# JTAG_Connector.net
KiCad netlist of a schematic drawn in Altium Designer
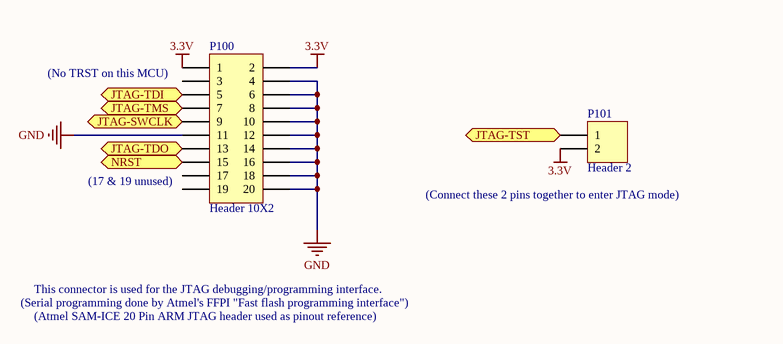
[diagram p0: JTAG_Connector.SchDoc]

(export (version "E")
  (design (tool "Eeschema 10.0.6"))
  (components
    (comp (ref "P100")
      (value "Header 10X2")
      (footprint "HDR2X10")
      (description "Header, 10-Pin, Dual row")
      (fields (field (name "PUBLISHER") "Altium Limited"))
      (libsource (lib "Miscellaneous Connectors") (part "Header 10X2"))
    )
    (comp (ref "P101")
      (value "Header 2")
      (footprint "HDR1X2")
      (description "Header, 2-Pin")
      (fields (field (name "PUBLISHER") "Altium Limited"))
      (libsource (lib "Miscellaneous Connectors") (part "Header 2"))
    )
  )
  (nets
    (net (code "1") (name "/JTAG-SWCLK") (class "Default")
      (node (ref "P100") (pin "9") (pinfunction "9_9") (pintype "passive"))
    )
    (net (code "2") (name "/JTAG-TDI") (class "Default")
      (node (ref "P100") (pin "5") (pinfunction "5_5") (pintype "passive"))
    )
    (net (code "3") (name "/JTAG-TDO") (class "Default")
      (node (ref "P100") (pin "13") (pinfunction "13_13") (pintype "passive"))
    )
    (net (code "4") (name "/JTAG-TMS") (class "Default")
      (node (ref "P100") (pin "7") (pinfunction "7_7") (pintype "passive"))
    )
    (net (code "5") (name "/JTAG-TST") (class "Default")
      (node (ref "P101") (pin "1") (pinfunction "1_1") (pintype "passive"))
    )
    (net (code "6") (name "/NRST") (class "Default")
      (node (ref "P100") (pin "15") (pinfunction "15_15") (pintype "passive"))
    )
    (net (code "7") (name "3.3V") (class "Default")
      (node (ref "P100") (pin "1") (pinfunction "1_1") (pintype "passive"))
      (node (ref "P100") (pin "2") (pinfunction "2_2") (pintype "passive"))
      (node (ref "P101") (pin "2") (pinfunction "2_2") (pintype "passive"))
    )
    (net (code "8") (name "GND") (class "Default")
      (node (ref "P100") (pin "10") (pinfunction "10_10") (pintype "passive"))
      (node (ref "P100") (pin "11") (pinfunction "11_11") (pintype "passive"))
      (node (ref "P100") (pin "12") (pinfunction "12_12") (pintype "passive"))
      (node (ref "P100") (pin "14") (pinfunction "14_14") (pintype "passive"))
      (node (ref "P100") (pin "16") (pinfunction "16_16") (pintype "passive"))
      (node (ref "P100") (pin "18") (pinfunction "18_18") (pintype "passive"))
      (node (ref "P100") (pin "20") (pinfunction "20_20") (pintype "passive"))
      (node (ref "P100") (pin "4") (pinfunction "4_4") (pintype "passive"))
      (node (ref "P100") (pin "6") (pinfunction "6_6") (pintype "passive"))
      (node (ref "P100") (pin "8") (pinfunction "8_8") (pintype "passive"))
    )
    (net (code "9") (name "unconnected-(P100-Pad3)") (class "Default")
      (node (ref "P100") (pin "3") (pinfunction "3_3") (pintype "passive"))
    )
    (net (code "10") (name "unconnected-(P100-Pad17)") (class "Default")
      (node (ref "P100") (pin "17") (pinfunction "17_17") (pintype "passive"))
    )
    (net (code "11") (name "unconnected-(P100-Pad19)") (class "Default")
      (node (ref "P100") (pin "19") (pinfunction "19_19") (pintype "passive"))
    )
  )
)
